# TweakTone_V1-2.net
KiCad netlist of a schematic drawn in EAGLE
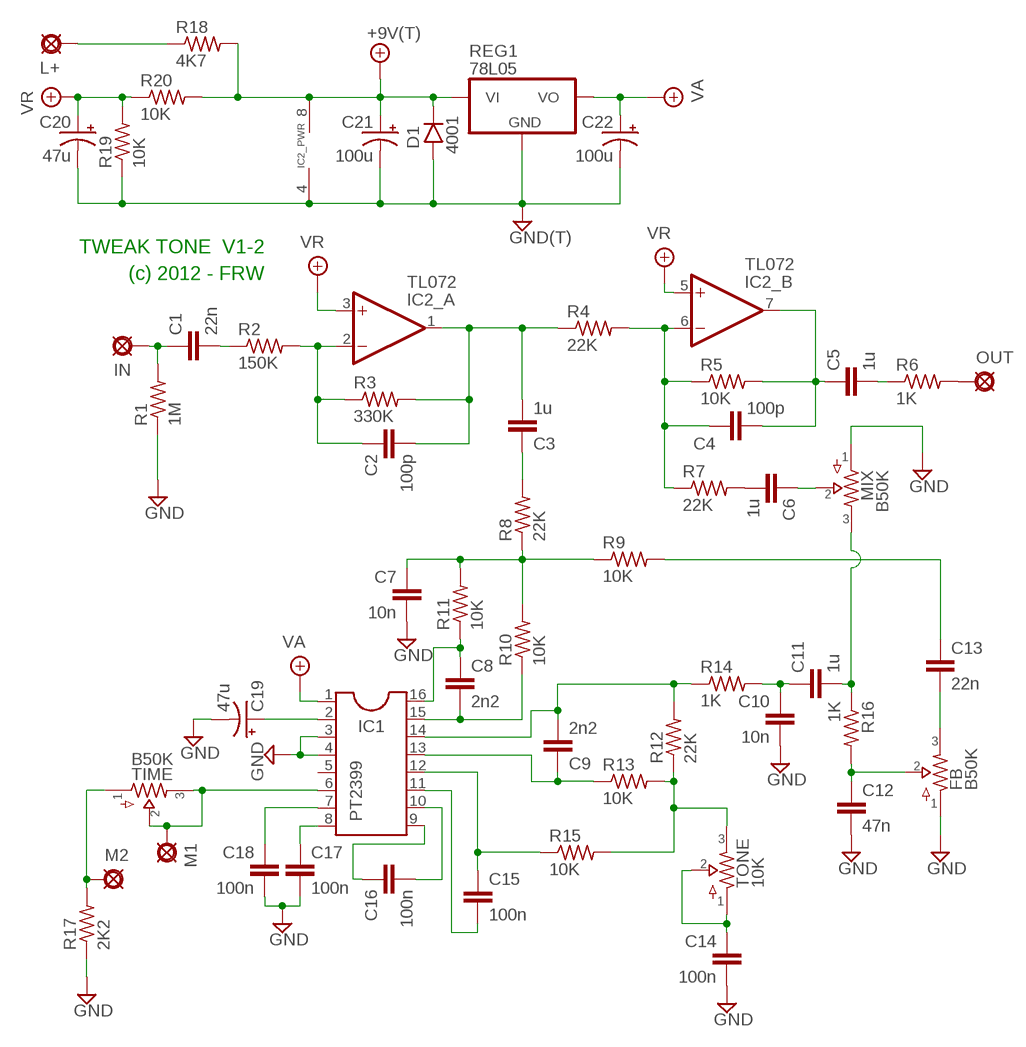
[diagram p0: schematic, sheet 1]

(export (version "E")
  (design (tool "Eeschema 10.0.6"))
  (components
    (comp (ref "+9V")
      (value "+9V(T)")
      (footprint "eagle-import:SQUARE")
      (libsource (lib "eagle-import") (part "+9V(T)"))
    )
    (comp (ref "C1")
      (value "22n")
      (footprint "eagle-import:072X025")
      (libsource (lib "eagle-import") (part "072X0252"))
    )
    (comp (ref "C2")
      (value "100p")
      (footprint "eagle-import:050X030_025")
      (libsource (lib "eagle-import") (part "050X030_0251"))
    )
    (comp (ref "C3")
      (value "1u")
      (footprint "eagle-import:072X045")
      (libsource (lib "eagle-import") (part "072X0452"))
    )
    (comp (ref "C4")
      (value "100p")
      (footprint "eagle-import:050X030_025")
      (libsource (lib "eagle-import") (part "050X030_0251"))
    )
    (comp (ref "C5")
      (value "1u")
      (footprint "eagle-import:072X045")
      (libsource (lib "eagle-import") (part "072X0452"))
    )
    (comp (ref "C6")
      (value "1u")
      (footprint "eagle-import:072X045")
      (libsource (lib "eagle-import") (part "072X0452"))
    )
    (comp (ref "C7")
      (value "10n")
      (footprint "eagle-import:072X025")
      (libsource (lib "eagle-import") (part "072X0252"))
    )
    (comp (ref "C8")
      (value "2n2")
      (footprint "eagle-import:072X025")
      (libsource (lib "eagle-import") (part "072X0252"))
    )
    (comp (ref "C9")
      (value "2n2")
      (footprint "eagle-import:072X025")
      (libsource (lib "eagle-import") (part "072X0252"))
    )
    (comp (ref "C10")
      (value "10n")
      (footprint "eagle-import:072X025")
      (libsource (lib "eagle-import") (part "072X0252"))
    )
    (comp (ref "C11")
      (value "1u")
      (footprint "eagle-import:072X045")
      (libsource (lib "eagle-import") (part "072X0452"))
    )
    (comp (ref "C12")
      (value "47n")
      (footprint "eagle-import:072X025")
      (libsource (lib "eagle-import") (part "072X0252"))
    )
    (comp (ref "C13")
      (value "22n")
      (footprint "eagle-import:072X025")
      (libsource (lib "eagle-import") (part "072X0252"))
    )
    (comp (ref "C14")
      (value "100n")
      (footprint "eagle-import:072X025")
      (libsource (lib "eagle-import") (part "072X0252"))
    )
    (comp (ref "C15")
      (value "100n")
      (footprint "eagle-import:SMALL-5MM")
      (libsource (lib "eagle-import") (part "CAPS_BOX_SMALL"))
    )
    (comp (ref "C16")
      (value "100n")
      (footprint "eagle-import:SMALL-5MM")
      (libsource (lib "eagle-import") (part "CAPS_BOX_SMALL"))
    )
    (comp (ref "C17")
      (value "100n")
      (footprint "eagle-import:SMALL-5MM")
      (libsource (lib "eagle-import") (part "CAPS_BOX_SMALL"))
    )
    (comp (ref "C18")
      (value "100n")
      (footprint "eagle-import:SMALL-5MM")
      (libsource (lib "eagle-import") (part "CAPS_BOX_SMALL"))
    )
    (comp (ref "C19")
      (value "47u")
      (footprint "eagle-import:050_020_1")
      (libsource (lib "eagle-import") (part "0501"))
    )
    (comp (ref "C20")
      (value "47u")
      (footprint "eagle-import:050_020_1")
      (libsource (lib "eagle-import") (part "0501"))
    )
    (comp (ref "C21")
      (value "100u")
      (footprint "eagle-import:050_020_1")
      (libsource (lib "eagle-import") (part "0501"))
    )
    (comp (ref "C22")
      (value "100u")
      (footprint "eagle-import:050_020_1")
      (libsource (lib "eagle-import") (part "0501"))
    )
    (comp (ref "D1")
      (value "4001")
      (footprint "eagle-import:DO41-3")
      (libsource (lib "eagle-import") (part "1N400X.3"))
    )
    (comp (ref "FB")
      (value "B50K")
      (footprint "eagle-import:16MM")
      (libsource (lib "eagle-import") (part "POTS16MM"))
    )
    (comp (ref "GND")
      (value "GND(T)")
      (footprint "eagle-import:SQUARE")
      (libsource (lib "eagle-import") (part "GND(T)"))
    )
    (comp (ref "IC1")
      (value "PT2399")
      (footprint "eagle-import:DIL16")
      (libsource (lib "eagle-import") (part "DIL16"))
    )
    (comp (ref "IC2")
      (value "TL072")
      (footprint "eagle-import:DIL08")
      (libsource (lib "eagle-import") (part "DUALTH"))
    )
    (comp (ref "IN")
      (value "IN")
      (footprint "eagle-import:SQUARE")
      (libsource (lib "eagle-import") (part "gm-supply_PAD"))
    )
    (comp (ref "L+")
      (value "IN")
      (footprint "eagle-import:SQUARE")
      (libsource (lib "eagle-import") (part "gm-supply_PAD"))
    )
    (comp (ref "M1")
      (value "PAD8")
      (footprint "eagle-import:OCTOGON")
      (libsource (lib "eagle-import") (part "PAD8"))
    )
    (comp (ref "M2")
      (value "PAD8")
      (footprint "eagle-import:OCTOGON")
      (libsource (lib "eagle-import") (part "PAD8"))
    )
    (comp (ref "MIX")
      (value "B50K")
      (footprint "eagle-import:16MM")
      (libsource (lib "eagle-import") (part "POTS16MM"))
    )
    (comp (ref "OUT")
      (value "out")
      (footprint "eagle-import:SQUARE")
      (libsource (lib "eagle-import") (part "gm-supply_PAD"))
    )
    (comp (ref "R1")
      (value "1M")
      (footprint "eagle-import:R0207_3")
      (libsource (lib "eagle-import") (part "6MM.3"))
    )
    (comp (ref "R2")
      (value "150K")
      (footprint "eagle-import:R0207_3")
      (libsource (lib "eagle-import") (part "6MM.3"))
    )
    (comp (ref "R3")
      (value "330K")
      (footprint "eagle-import:R0207_3")
      (libsource (lib "eagle-import") (part "6MM.3"))
    )
    (comp (ref "R4")
      (value "22K")
      (footprint "eagle-import:R0207_3")
      (libsource (lib "eagle-import") (part "6MM.3"))
    )
    (comp (ref "R5")
      (value "10K")
      (footprint "eagle-import:R0207_3")
      (libsource (lib "eagle-import") (part "6MM.3"))
    )
    (comp (ref "R6")
      (value "1K")
      (footprint "eagle-import:R0207_3")
      (libsource (lib "eagle-import") (part "6MM.3"))
    )
    (comp (ref "R7")
      (value "22K")
      (footprint "eagle-import:R0207_3")
      (libsource (lib "eagle-import") (part "6MM.3"))
    )
    (comp (ref "R8")
      (value "22K")
      (footprint "eagle-import:R0207_3")
      (libsource (lib "eagle-import") (part "6MM.3"))
    )
    (comp (ref "R9")
      (value "10K")
      (footprint "eagle-import:R0207_3")
      (libsource (lib "eagle-import") (part "6MM.3"))
    )
    (comp (ref "R10")
      (value "10K")
      (footprint "eagle-import:R0207_3")
      (libsource (lib "eagle-import") (part "6MM.3"))
    )
    (comp (ref "R11")
      (value "10K")
      (footprint "eagle-import:R0207_3")
      (libsource (lib "eagle-import") (part "6MM.3"))
    )
    (comp (ref "R12")
      (value "22K")
      (footprint "eagle-import:R0207_3")
      (libsource (lib "eagle-import") (part "6MM.3"))
    )
    (comp (ref "R13")
      (value "10K")
      (footprint "eagle-import:R0207_3")
      (libsource (lib "eagle-import") (part "6MM.3"))
    )
    (comp (ref "R14")
      (value "1K")
      (footprint "eagle-import:R0207_3")
      (libsource (lib "eagle-import") (part "6MM.3"))
    )
    (comp (ref "R15")
      (value "10K")
      (footprint "eagle-import:R0207_3")
      (libsource (lib "eagle-import") (part "6MM.3"))
    )
    (comp (ref "R16")
      (value "1K")
      (footprint "eagle-import:R0207_3")
      (libsource (lib "eagle-import") (part "6MM.3"))
    )
    (comp (ref "R17")
      (value "2K2")
      (footprint "eagle-import:R0207_3")
      (libsource (lib "eagle-import") (part "6MM.3"))
    )
    (comp (ref "R18")
      (value "4K7")
      (footprint "eagle-import:R0207_3")
      (libsource (lib "eagle-import") (part "6MM.3"))
    )
    (comp (ref "R19")
      (value "10K")
      (footprint "eagle-import:R0207_3")
      (libsource (lib "eagle-import") (part "6MM.3"))
    )
    (comp (ref "R20")
      (value "10K")
      (footprint "eagle-import:R0207_3")
      (libsource (lib "eagle-import") (part "6MM.3"))
    )
    (comp (ref "REG1")
      (value "78L05")
      (footprint "eagle-import:TO92-")
      (libsource (lib "eagle-import") (part "78L05"))
    )
    (comp (ref "TIME")
      (value "B50K")
      (footprint "eagle-import:16MM")
      (libsource (lib "eagle-import") (part "POTS16MM"))
    )
    (comp (ref "TONE")
      (value "10K")
      (footprint "eagle-import:2262_TRIM")
      (libsource (lib "eagle-import") (part "POTSTRIM"))
    )
  )
  (nets
    (net (code "1") (name "+9V(T)") (class "Default")
      (node (ref "+9V") (pin "1") (pinfunction "+9V_1") (pintype "power_in"))
      (node (ref "C21") (pin "+") (pinfunction "+_+") (pintype "passive"))
      (node (ref "D1") (pin "C") (pinfunction "C_C") (pintype "passive"))
      (node (ref "IC2") (pin "8") (pinfunction "V+_8") (pintype "power_in"))
      (node (ref "R18") (pin "2") (pinfunction "2_2") (pintype "passive"))
      (node (ref "R20") (pin "2") (pinfunction "2_2") (pintype "passive"))
      (node (ref "REG1") (pin "1") (pinfunction "VI_1") (pintype "input"))
    )
    (net (code "2") (name "GND") (class "Default")
      (node (ref "C10") (pin "2") (pinfunction "2_2") (pintype "passive"))
      (node (ref "C12") (pin "2") (pinfunction "2_2") (pintype "passive"))
      (node (ref "C14") (pin "2") (pinfunction "2_2") (pintype "passive"))
      (node (ref "C17") (pin "2") (pinfunction "2_2") (pintype "passive"))
      (node (ref "C18") (pin "2") (pinfunction "2_2") (pintype "passive"))
      (node (ref "C19") (pin "-") (pinfunction "-_-") (pintype "passive"))
      (node (ref "C20") (pin "-") (pinfunction "-_-") (pintype "passive"))
      (node (ref "C21") (pin "-") (pinfunction "-_-") (pintype "passive"))
      (node (ref "C22") (pin "-") (pinfunction "-_-") (pintype "passive"))
      (node (ref "C7") (pin "2") (pinfunction "2_2") (pintype "passive"))
      (node (ref "D1") (pin "A") (pinfunction "A_A") (pintype "passive"))
      (node (ref "FB") (pin "1") (pinfunction "1_1") (pintype "passive"))
      (node (ref "GND") (pin "1") (pinfunction "GND_1") (pintype "power_in"))
      (node (ref "IC1") (pin "3") (pinfunction "3_3") (pintype "passive"))
      (node (ref "IC1") (pin "4") (pinfunction "4_4") (pintype "passive"))
      (node (ref "IC2") (pin "4") (pinfunction "V-_4") (pintype "power_in"))
      (node (ref "MIX") (pin "1") (pinfunction "1_1") (pintype "passive"))
      (node (ref "R1") (pin "1") (pinfunction "1_1") (pintype "passive"))
      (node (ref "R17") (pin "1") (pinfunction "1_1") (pintype "passive"))
      (node (ref "R19") (pin "1") (pinfunction "1_1") (pintype "passive"))
      (node (ref "REG1") (pin "2") (pinfunction "GND_2") (pintype "passive"))
    )
    (net (code "3") (name "Net-(C1-Pad2)") (class "Default")
      (node (ref "C1") (pin "2") (pinfunction "2_2") (pintype "passive"))
      (node (ref "R2") (pin "1") (pinfunction "1_1") (pintype "passive"))
    )
    (net (code "4") (name "Net-(C3-Pad1)") (class "Default")
      (node (ref "C3") (pin "1") (pinfunction "1_1") (pintype "passive"))
      (node (ref "R8") (pin "2") (pinfunction "2_2") (pintype "passive"))
    )
    (net (code "5") (name "Net-(C5-Pad2)") (class "Default")
      (node (ref "C5") (pin "2") (pinfunction "2_2") (pintype "passive"))
      (node (ref "R6") (pin "1") (pinfunction "1_1") (pintype "passive"))
    )
    (net (code "6") (name "Net-(C6-Pad1)") (class "Default")
      (node (ref "C6") (pin "1") (pinfunction "1_1") (pintype "passive"))
      (node (ref "MIX") (pin "2") (pinfunction "2_2") (pintype "passive"))
    )
    (net (code "7") (name "Net-(C6-Pad2)") (class "Default")
      (node (ref "C6") (pin "2") (pinfunction "2_2") (pintype "passive"))
      (node (ref "R7") (pin "2") (pinfunction "2_2") (pintype "passive"))
    )
    (net (code "8") (name "Net-(C7-Pad1)") (class "Default")
      (node (ref "C7") (pin "1") (pinfunction "1_1") (pintype "passive"))
      (node (ref "R10") (pin "2") (pinfunction "2_2") (pintype "passive"))
      (node (ref "R11") (pin "2") (pinfunction "2_2") (pintype "passive"))
      (node (ref "R8") (pin "1") (pinfunction "1_1") (pintype "passive"))
      (node (ref "R9") (pin "1") (pinfunction "1_1") (pintype "passive"))
    )
    (net (code "9") (name "Net-(C8-Pad1)") (class "Default")
      (node (ref "C8") (pin "1") (pinfunction "1_1") (pintype "passive"))
      (node (ref "IC1") (pin "16") (pinfunction "16_16") (pintype "passive"))
      (node (ref "R11") (pin "1") (pinfunction "1_1") (pintype "passive"))
    )
    (net (code "10") (name "Net-(C8-Pad2)") (class "Default")
      (node (ref "C8") (pin "2") (pinfunction "2_2") (pintype "passive"))
      (node (ref "IC1") (pin "15") (pinfunction "15_15") (pintype "passive"))
      (node (ref "R10") (pin "1") (pinfunction "1_1") (pintype "passive"))
    )
    (net (code "11") (name "Net-(C9-Pad1)") (class "Default")
      (node (ref "C9") (pin "1") (pinfunction "1_1") (pintype "passive"))
      (node (ref "IC1") (pin "13") (pinfunction "13_13") (pintype "passive"))
      (node (ref "R13") (pin "1") (pinfunction "1_1") (pintype "passive"))
    )
    (net (code "12") (name "Net-(C9-Pad2)") (class "Default")
      (node (ref "C9") (pin "2") (pinfunction "2_2") (pintype "passive"))
      (node (ref "IC1") (pin "14") (pinfunction "14_14") (pintype "passive"))
      (node (ref "R12") (pin "2") (pinfunction "2_2") (pintype "passive"))
      (node (ref "R14") (pin "1") (pinfunction "1_1") (pintype "passive"))
    )
    (net (code "13") (name "Net-(C10-Pad1)") (class "Default")
      (node (ref "C10") (pin "1") (pinfunction "1_1") (pintype "passive"))
      (node (ref "C11") (pin "1") (pinfunction "1_1") (pintype "passive"))
      (node (ref "R14") (pin "2") (pinfunction "2_2") (pintype "passive"))
    )
    (net (code "14") (name "Net-(C11-Pad2)") (class "Default")
      (node (ref "C11") (pin "2") (pinfunction "2_2") (pintype "passive"))
      (node (ref "MIX") (pin "3") (pinfunction "3_3") (pintype "passive"))
      (node (ref "R16") (pin "1") (pinfunction "1_1") (pintype "passive"))
    )
    (net (code "15") (name "Net-(C12-Pad1)") (class "Default")
      (node (ref "C12") (pin "1") (pinfunction "1_1") (pintype "passive"))
      (node (ref "FB") (pin "2") (pinfunction "2_2") (pintype "passive"))
      (node (ref "R16") (pin "2") (pinfunction "2_2") (pintype "passive"))
    )
    (net (code "16") (name "Net-(C13-Pad1)") (class "Default")
      (node (ref "C13") (pin "1") (pinfunction "1_1") (pintype "passive"))
      (node (ref "R9") (pin "2") (pinfunction "2_2") (pintype "passive"))
    )
    (net (code "17") (name "Net-(C13-Pad2)") (class "Default")
      (node (ref "C13") (pin "2") (pinfunction "2_2") (pintype "passive"))
      (node (ref "FB") (pin "3") (pinfunction "3_3") (pintype "passive"))
    )
    (net (code "18") (name "Net-(C14-Pad1)") (class "Default")
      (node (ref "C14") (pin "1") (pinfunction "1_1") (pintype "passive"))
      (node (ref "TONE") (pin "1") (pinfunction "1_1") (pintype "passive"))
      (node (ref "TONE") (pin "2") (pinfunction "2_2") (pintype "passive"))
    )
    (net (code "19") (name "Net-(C15-Pad1)") (class "Default")
      (node (ref "C15") (pin "1") (pinfunction "1_1") (pintype "passive"))
      (node (ref "IC1") (pin "12") (pinfunction "12_12") (pintype "passive"))
      (node (ref "R15") (pin "1") (pinfunction "1_1") (pintype "passive"))
    )
    (net (code "20") (name "Net-(C15-Pad2)") (class "Default")
      (node (ref "C15") (pin "2") (pinfunction "2_2") (pintype "passive"))
      (node (ref "IC1") (pin "11") (pinfunction "11_11") (pintype "passive"))
    )
    (net (code "21") (name "Net-(C16-Pad1)") (class "Default")
      (node (ref "C16") (pin "1") (pinfunction "1_1") (pintype "passive"))
      (node (ref "IC1") (pin "9") (pinfunction "9_9") (pintype "passive"))
    )
    (net (code "22") (name "Net-(C16-Pad2)") (class "Default")
      (node (ref "C16") (pin "2") (pinfunction "2_2") (pintype "passive"))
      (node (ref "IC1") (pin "10") (pinfunction "10_10") (pintype "passive"))
    )
    (net (code "23") (name "Net-(C17-Pad1)") (class "Default")
      (node (ref "C17") (pin "1") (pinfunction "1_1") (pintype "passive"))
      (node (ref "IC1") (pin "8") (pinfunction "8_8") (pintype "passive"))
    )
    (net (code "24") (name "Net-(C18-Pad1)") (class "Default")
      (node (ref "C18") (pin "1") (pinfunction "1_1") (pintype "passive"))
      (node (ref "IC1") (pin "7") (pinfunction "7_7") (pintype "passive"))
    )
    (net (code "25") (name "Net-(C19-Pad+)") (class "Default")
      (node (ref "C19") (pin "+") (pinfunction "+_+") (pintype "passive"))
      (node (ref "IC1") (pin "2") (pinfunction "2_2") (pintype "passive"))
    )
    (net (code "26") (name "Net-(IC2A--IN)") (class "Default")
      (node (ref "C2") (pin "1") (pinfunction "1_1") (pintype "passive"))
      (node (ref "IC2") (pin "2") (pinfunction "-IN_2") (pintype "input"))
      (node (ref "R2") (pin "2") (pinfunction "2_2") (pintype "passive"))
      (node (ref "R3") (pin "1") (pinfunction "1_1") (pintype "passive"))
    )
    (net (code "27") (name "Net-(IC2A-OUT)") (class "Default")
      (node (ref "C2") (pin "2") (pinfunction "2_2") (pintype "passive"))
      (node (ref "C3") (pin "2") (pinfunction "2_2") (pintype "passive"))
      (node (ref "IC2") (pin "1") (pinfunction "OUT_1") (pintype "output"))
      (node (ref "R3") (pin "2") (pinfunction "2_2") (pintype "passive"))
      (node (ref "R4") (pin "1") (pinfunction "1_1") (pintype "passive"))
    )
    (net (code "28") (name "Net-(IC2B--IN)") (class "Default")
      (node (ref "C4") (pin "1") (pinfunction "1_1") (pintype "passive"))
      (node (ref "IC2") (pin "6") (pinfunction "-IN_6") (pintype "input"))
      (node (ref "R4") (pin "2") (pinfunction "2_2") (pintype "passive"))
      (node (ref "R5") (pin "1") (pinfunction "1_1") (pintype "passive"))
      (node (ref "R7") (pin "1") (pinfunction "1_1") (pintype "passive"))
    )
    (net (code "29") (name "Net-(IC2B-OUT)") (class "Default")
      (node (ref "C4") (pin "2") (pinfunction "2_2") (pintype "passive"))
      (node (ref "C5") (pin "1") (pinfunction "1_1") (pintype "passive"))
      (node (ref "IC2") (pin "7") (pinfunction "OUT_7") (pintype "output"))
      (node (ref "R5") (pin "2") (pinfunction "2_2") (pintype "passive"))
    )
    (net (code "30") (name "Net-(IN-PAD)") (class "Default")
      (node (ref "C1") (pin "1") (pinfunction "1_1") (pintype "passive"))
      (node (ref "IN") (pin "1") (pinfunction "PAD_1") (pintype "passive"))
      (node (ref "R1") (pin "2") (pinfunction "2_2") (pintype "passive"))
    )
    (net (code "31") (name "Net-(L+-PAD)") (class "Default")
      (node (ref "L+") (pin "1") (pinfunction "PAD_1") (pintype "passive"))
      (node (ref "R18") (pin "1") (pinfunction "1_1") (pintype "passive"))
    )
    (net (code "32") (name "Net-(M1-PAD)") (class "Default")
      (node (ref "IC1") (pin "6") (pinfunction "6_6") (pintype "passive"))
      (node (ref "M1") (pin "1") (pinfunction "PAD_1") (pintype "passive"))
      (node (ref "TIME") (pin "2") (pinfunction "2_2") (pintype "passive"))
      (node (ref "TIME") (pin "3") (pinfunction "3_3") (pintype "passive"))
    )
    (net (code "33") (name "Net-(M2-PAD)") (class "Default")
      (node (ref "M2") (pin "1") (pinfunction "PAD_1") (pintype "passive"))
      (node (ref "R17") (pin "2") (pinfunction "2_2") (pintype "passive"))
      (node (ref "TIME") (pin "1") (pinfunction "1_1") (pintype "passive"))
    )
    (net (code "34") (name "Net-(OUT-PAD)") (class "Default")
      (node (ref "OUT") (pin "1") (pinfunction "PAD_1") (pintype "passive"))
      (node (ref "R6") (pin "2") (pinfunction "2_2") (pintype "passive"))
    )
    (net (code "35") (name "Net-(R12-Pad1)") (class "Default")
      (node (ref "R12") (pin "1") (pinfunction "1_1") (pintype "passive"))
      (node (ref "R13") (pin "2") (pinfunction "2_2") (pintype "passive"))
      (node (ref "R15") (pin "2") (pinfunction "2_2") (pintype "passive"))
      (node (ref "TONE") (pin "3") (pinfunction "3_3") (pintype "passive"))
    )
    (net (code "36") (name "VA") (class "Default")
      (node (ref "C22") (pin "+") (pinfunction "+_+") (pintype "passive"))
      (node (ref "IC1") (pin "1") (pinfunction "1_1") (pintype "passive"))
      (node (ref "REG1") (pin "3") (pinfunction "VO_3") (pintype "passive"))
    )
    (net (code "37") (name "VR") (class "Default")
      (node (ref "C20") (pin "+") (pinfunction "+_+") (pintype "passive"))
      (node (ref "IC2") (pin "3") (pinfunction "+IN_3") (pintype "input"))
      (node (ref "IC2") (pin "5") (pinfunction "+IN_5") (pintype "input"))
      (node (ref "R19") (pin "2") (pinfunction "2_2") (pintype "passive"))
      (node (ref "R20") (pin "1") (pinfunction "1_1") (pintype "passive"))
    )
    (net (code "38") (name "unconnected-(IC1-Pad5)") (class "Default")
      (node (ref "IC1") (pin "5") (pinfunction "5_5") (pintype "passive"))
    )
  )
)
